# v1microcontroller.net
KiCad netlist of a schematic drawn in EAGLE
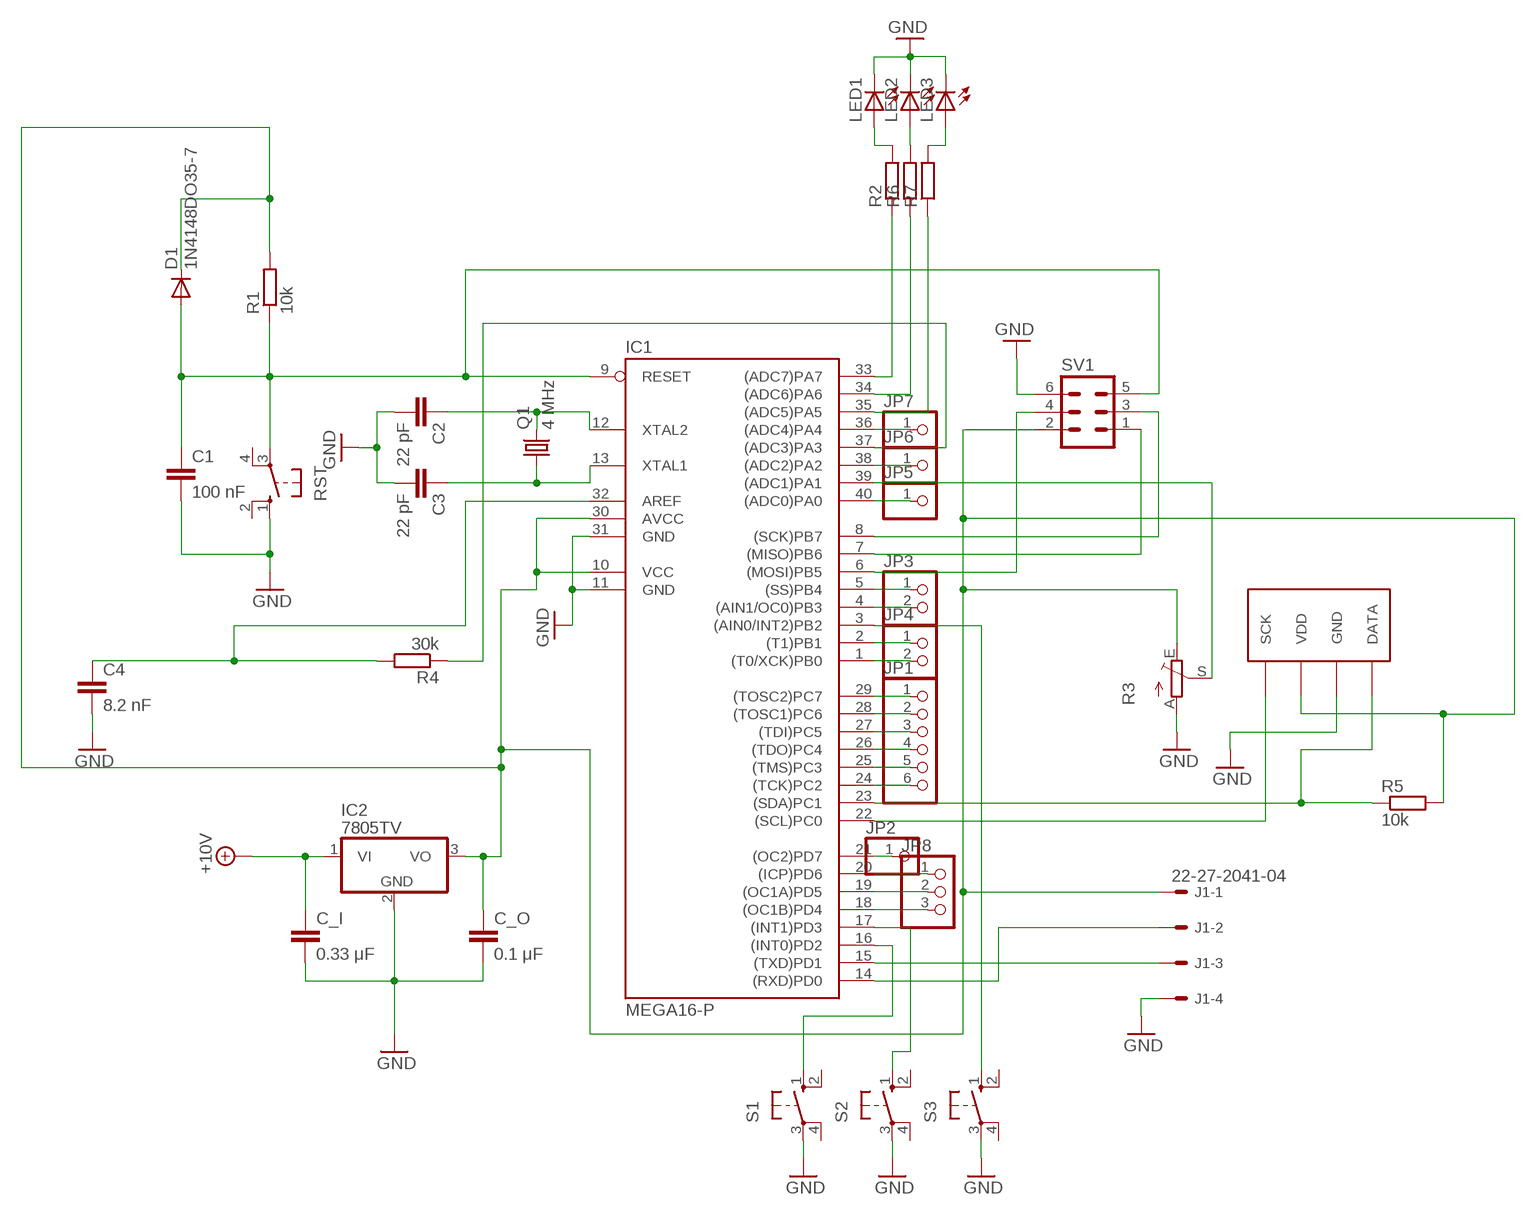
[diagram p0: schematic, sheet 1]

(export (version "E")
  (design (tool "Eeschema 10.0.6"))
  (components
    (comp (ref "C1")
      (value "100 nF")
      (footprint "eagle-import:C2.5-3")
      (libsource (lib "eagle-import") (part "C2,5-3"))
    )
    (comp (ref "C2")
      (value "22 pF")
      (footprint "eagle-import:C2.5-3")
      (libsource (lib "eagle-import") (part "C2,5-3"))
    )
    (comp (ref "C3")
      (value "22 pF")
      (footprint "eagle-import:C2.5-3")
      (libsource (lib "eagle-import") (part "C2,5-3"))
    )
    (comp (ref "C4")
      (value "8.2 nF")
      (footprint "eagle-import:C2.5-3")
      (libsource (lib "eagle-import") (part "C2,5-3"))
    )
    (comp (ref "C_I")
      (value "0.33 μF")
      (footprint "eagle-import:C2.5-3")
      (libsource (lib "eagle-import") (part "C2,5-3"))
    )
    (comp (ref "C_O")
      (value "0.1 μF")
      (footprint "eagle-import:C2.5-3")
      (libsource (lib "eagle-import") (part "C2,5-3"))
    )
    (comp (ref "D1")
      (value "1N4148DO35-7")
      (footprint "eagle-import:DO35-7")
      (libsource (lib "eagle-import") (part "1N4148DO35-7"))
    )
    (comp (ref "IC1")
      (value "MEGA16-P")
      (footprint "eagle-import:DIL40")
      (fields (field (name "MPN") "ATMEGA16-16PU"))
      (libsource (lib "eagle-import") (part "MEGA16-P"))
    )
    (comp (ref "IC2")
      (value "7805TV")
      (footprint "eagle-import:TO220V")
      (fields (field (name "SPICEPREFIX") "J"))
      (libsource (lib "eagle-import") (part "78TV05"))
    )
    (comp (ref "J1")
      (value "22-27-2041-04")
      (footprint "eagle-import:6410-04")
      (fields (field (name "MF") "MOLEX"))
      (libsource (lib "eagle-import") (part "22-?-0427-2041"))
    )
    (comp (ref "JP1")
      (value "PINHD-1X6")
      (footprint "eagle-import:1X06")
      (libsource (lib "eagle-import") (part "PINHD-1X6"))
    )
    (comp (ref "JP2")
      (value "PINHD-1X1")
      (footprint "eagle-import:1X01")
      (libsource (lib "eagle-import") (part "PINHD-1X1"))
    )
    (comp (ref "JP3")
      (value "PINHD-1X2")
      (footprint "eagle-import:1X02")
      (libsource (lib "eagle-import") (part "PINHD-1X2"))
    )
    (comp (ref "JP4")
      (value "PINHD-1X2")
      (footprint "eagle-import:1X02")
      (libsource (lib "eagle-import") (part "PINHD-1X2"))
    )
    (comp (ref "JP5")
      (value "PINHD-1X1")
      (footprint "eagle-import:1X01")
      (libsource (lib "eagle-import") (part "PINHD-1X1"))
    )
    (comp (ref "JP6")
      (value "PINHD-1X1")
      (footprint "eagle-import:1X01")
      (libsource (lib "eagle-import") (part "PINHD-1X1"))
    )
    (comp (ref "JP7")
      (value "PINHD-1X1")
      (footprint "eagle-import:1X01")
      (libsource (lib "eagle-import") (part "PINHD-1X1"))
    )
    (comp (ref "JP8")
      (value "PINHD-1X3")
      (footprint "eagle-import:1X03")
      (libsource (lib "eagle-import") (part "PINHD-1X3"))
    )
    (comp (ref "LED1")
      (value "LED5MM")
      (footprint "eagle-import:LED5MM")
      (libsource (lib "eagle-import") (part "LED5MM"))
    )
    (comp (ref "LED2")
      (value "LED5MM")
      (footprint "eagle-import:LED5MM")
      (libsource (lib "eagle-import") (part "LED5MM"))
    )
    (comp (ref "LED3")
      (value "LED5MM")
      (footprint "eagle-import:LED5MM")
      (libsource (lib "eagle-import") (part "LED5MM"))
    )
    (comp (ref "Q1")
      (value "4 MHz")
      (footprint "eagle-import:HC49U-V")
      (libsource (lib "eagle-import") (part "CRYSTALHC49U-V"))
    )
    (comp (ref "R1")
      (value "10k")
      (footprint "eagle-import:0204_5")
      (libsource (lib "eagle-import") (part "R-EU_0204/5"))
    )
    (comp (ref "R2")
      (value "R-EU_0204/5")
      (footprint "eagle-import:0204_5")
      (libsource (lib "eagle-import") (part "R-EU_0204/5"))
    )
    (comp (ref "R3")
      (value "TRIM_EU-CT6")
      (footprint "eagle-import:CT6")
      (libsource (lib "eagle-import") (part "TRIM_EU-CT6"))
    )
    (comp (ref "R4")
      (value "30k")
      (footprint "eagle-import:0204_5")
      (libsource (lib "eagle-import") (part "R-EU_0204/5"))
    )
    (comp (ref "R5")
      (value "10k")
      (footprint "eagle-import:0204_5")
      (libsource (lib "eagle-import") (part "R-EU_0204/5"))
    )
    (comp (ref "R6")
      (value "R-EU_0204/5")
      (footprint "eagle-import:0204_5")
      (libsource (lib "eagle-import") (part "R-EU_0204/5"))
    )
    (comp (ref "R7")
      (value "R-EU_0204/5")
      (footprint "eagle-import:0204_5")
      (libsource (lib "eagle-import") (part "R-EU_0204/5"))
    )
    (comp (ref "RST")
      (value "10-XX")
      (footprint "eagle-import:B3F-10XX")
      (fields (field (name "MPN") "B3F-1000"))
      (libsource (lib "eagle-import") (part "10-XX"))
    )
    (comp (ref "S1")
      (value "10-XX")
      (footprint "eagle-import:B3F-10XX")
      (fields (field (name "MPN") "B3F-1000"))
      (libsource (lib "eagle-import") (part "10-XX"))
    )
    (comp (ref "S2")
      (value "10-XX")
      (footprint "eagle-import:B3F-10XX")
      (fields (field (name "MPN") "B3F-1000"))
      (libsource (lib "eagle-import") (part "10-XX"))
    )
    (comp (ref "S3")
      (value "10-XX")
      (footprint "eagle-import:B3F-10XX")
      (fields (field (name "MPN") "B3F-1000"))
      (libsource (lib "eagle-import") (part "10-XX"))
    )
    (comp (ref "SV1")
      (value "ML6")
      (footprint "eagle-import:ML6")
      (libsource (lib "eagle-import") (part "ML6"))
    )
    (comp (ref "U$1")
      (value "SHT71")
      (footprint "eagle-import:SHT7X")
      (libsource (lib "eagle-import") (part "SHT71"))
    )
  )
  (nets
    (net (code "1") (name "+10V") (class "Default")
      (node (ref "C_I") (pin "1") (pinfunction "1_1") (pintype "passive"))
      (node (ref "IC2") (pin "1") (pinfunction "VI_1") (pintype "input"))
    )
    (net (code "2") (name "GND") (class "Default")
      (node (ref "C1") (pin "2") (pinfunction "2_2") (pintype "passive"))
      (node (ref "C2") (pin "2") (pinfunction "2_2") (pintype "passive"))
      (node (ref "C3") (pin "2") (pinfunction "2_2") (pintype "passive"))
      (node (ref "C4") (pin "2") (pinfunction "2_2") (pintype "passive"))
      (node (ref "C_I") (pin "2") (pinfunction "2_2") (pintype "passive"))
      (node (ref "C_O") (pin "2") (pinfunction "2_2") (pintype "passive"))
      (node (ref "IC1") (pin "11") (pinfunction "GND_11") (pintype "power_in"))
      (node (ref "IC1") (pin "31") (pinfunction "GND_31") (pintype "power_in"))
      (node (ref "IC2") (pin "2") (pinfunction "GND_2") (pintype "passive"))
      (node (ref "J1") (pin "4") (pinfunction "S_4") (pintype "passive"))
      (node (ref "LED1") (pin "K") (pinfunction "C_K") (pintype "passive"))
      (node (ref "LED2") (pin "K") (pinfunction "C_K") (pintype "passive"))
      (node (ref "LED3") (pin "K") (pinfunction "C_K") (pintype "passive"))
      (node (ref "R3") (pin "A") (pinfunction "A_A") (pintype "passive"))
      (node (ref "RST") (pin "1") (pinfunction "S_1") (pintype "passive"))
      (node (ref "S1") (pin "3") (pinfunction "P_3") (pintype "passive"))
      (node (ref "S2") (pin "3") (pinfunction "P_3") (pintype "passive"))
      (node (ref "S3") (pin "3") (pinfunction "P_3") (pintype "passive"))
      (node (ref "SV1") (pin "6") (pinfunction "6_6") (pintype "passive"))
      (node (ref "U$1") (pin "3") (pinfunction "GND_3") (pintype "power_in"))
    )
    (net (code "3") (name "Net-(IC1-(ADC0)PA0)") (class "Default")
      (node (ref "IC1") (pin "40") (pinfunction "(ADC0)PA0_40") (pintype "bidirectional"))
      (node (ref "JP5") (pin "1") (pinfunction "1_1") (pintype "passive"))
    )
    (net (code "4") (name "Net-(IC1-(ADC1)PA1)") (class "Default")
      (node (ref "IC1") (pin "39") (pinfunction "(ADC1)PA1_39") (pintype "bidirectional"))
      (node (ref "R3") (pin "S") (pinfunction "S_S") (pintype "passive"))
    )
    (net (code "5") (name "Net-(IC1-(ADC2)PA2)") (class "Default")
      (node (ref "IC1") (pin "38") (pinfunction "(ADC2)PA2_38") (pintype "bidirectional"))
      (node (ref "JP6") (pin "1") (pinfunction "1_1") (pintype "passive"))
    )
    (net (code "6") (name "Net-(IC1-(ADC3)PA3)") (class "Default")
      (node (ref "IC1") (pin "37") (pinfunction "(ADC3)PA3_37") (pintype "bidirectional"))
      (node (ref "R4") (pin "1") (pinfunction "1_1") (pintype "passive"))
    )
    (net (code "7") (name "Net-(IC1-(ADC4)PA4)") (class "Default")
      (node (ref "IC1") (pin "36") (pinfunction "(ADC4)PA4_36") (pintype "bidirectional"))
      (node (ref "JP7") (pin "1") (pinfunction "1_1") (pintype "passive"))
    )
    (net (code "8") (name "Net-(IC1-(ADC5)PA5)") (class "Default")
      (node (ref "IC1") (pin "35") (pinfunction "(ADC5)PA5_35") (pintype "bidirectional"))
      (node (ref "R7") (pin "1") (pinfunction "1_1") (pintype "passive"))
    )
    (net (code "9") (name "Net-(IC1-(ADC6)PA6)") (class "Default")
      (node (ref "IC1") (pin "34") (pinfunction "(ADC6)PA6_34") (pintype "bidirectional"))
      (node (ref "R6") (pin "1") (pinfunction "1_1") (pintype "passive"))
    )
    (net (code "10") (name "Net-(IC1-(ADC7)PA7)") (class "Default")
      (node (ref "IC1") (pin "33") (pinfunction "(ADC7)PA7_33") (pintype "bidirectional"))
      (node (ref "R2") (pin "1") (pinfunction "1_1") (pintype "passive"))
    )
    (net (code "11") (name "Net-(IC1-(AIN0{slash}INT2)PB2)") (class "Default")
      (node (ref "IC1") (pin "3") (pinfunction "(AIN0/INT2)PB2_3") (pintype "bidirectional"))
      (node (ref "S3") (pin "1") (pinfunction "S_1") (pintype "passive"))
    )
    (net (code "12") (name "Net-(IC1-(AIN1{slash}OC0)PB3)") (class "Default")
      (node (ref "IC1") (pin "4") (pinfunction "(AIN1/OC0)PB3_4") (pintype "bidirectional"))
      (node (ref "JP3") (pin "2") (pinfunction "2_2") (pintype "passive"))
    )
    (net (code "13") (name "Net-(IC1-(ICP)PD6)") (class "Default")
      (node (ref "IC1") (pin "20") (pinfunction "(ICP)PD6_20") (pintype "bidirectional"))
      (node (ref "JP8") (pin "1") (pinfunction "1_1") (pintype "passive"))
    )
    (net (code "14") (name "Net-(IC1-(INT0)PD2)") (class "Default")
      (node (ref "IC1") (pin "16") (pinfunction "(INT0)PD2_16") (pintype "bidirectional"))
      (node (ref "S1") (pin "1") (pinfunction "S_1") (pintype "passive"))
    )
    (net (code "15") (name "Net-(IC1-(INT1)PD3)") (class "Default")
      (node (ref "IC1") (pin "17") (pinfunction "(INT1)PD3_17") (pintype "bidirectional"))
      (node (ref "S2") (pin "1") (pinfunction "S_1") (pintype "passive"))
    )
    (net (code "16") (name "Net-(IC1-(MISO)PB6)") (class "Default")
      (node (ref "IC1") (pin "7") (pinfunction "(MISO)PB6_7") (pintype "bidirectional"))
      (node (ref "SV1") (pin "1") (pinfunction "1_1") (pintype "passive"))
    )
    (net (code "17") (name "Net-(IC1-(MOSI)PB5)") (class "Default")
      (node (ref "IC1") (pin "6") (pinfunction "(MOSI)PB5_6") (pintype "bidirectional"))
      (node (ref "SV1") (pin "4") (pinfunction "4_4") (pintype "passive"))
    )
    (net (code "18") (name "Net-(IC1-(OC1A)PD5)") (class "Default")
      (node (ref "IC1") (pin "19") (pinfunction "(OC1A)PD5_19") (pintype "bidirectional"))
      (node (ref "JP8") (pin "2") (pinfunction "2_2") (pintype "passive"))
    )
    (net (code "19") (name "Net-(IC1-(OC1B)PD4)") (class "Default")
      (node (ref "IC1") (pin "18") (pinfunction "(OC1B)PD4_18") (pintype "bidirectional"))
      (node (ref "JP8") (pin "3") (pinfunction "3_3") (pintype "passive"))
    )
    (net (code "20") (name "Net-(IC1-(OC2)PD7)") (class "Default")
      (node (ref "IC1") (pin "21") (pinfunction "(OC2)PD7_21") (pintype "bidirectional"))
      (node (ref "JP2") (pin "1") (pinfunction "1_1") (pintype "passive"))
    )
    (net (code "21") (name "Net-(IC1-(RXD)PD0)") (class "Default")
      (node (ref "IC1") (pin "14") (pinfunction "(RXD)PD0_14") (pintype "bidirectional"))
      (node (ref "J1") (pin "2") (pinfunction "S_2") (pintype "passive"))
    )
    (net (code "22") (name "Net-(IC1-(SCK)PB7)") (class "Default")
      (node (ref "IC1") (pin "8") (pinfunction "(SCK)PB7_8") (pintype "bidirectional"))
      (node (ref "SV1") (pin "3") (pinfunction "3_3") (pintype "passive"))
    )
    (net (code "23") (name "Net-(IC1-(SCL)PC0)") (class "Default")
      (node (ref "IC1") (pin "22") (pinfunction "(SCL)PC0_22") (pintype "bidirectional"))
      (node (ref "U$1") (pin "1") (pinfunction "SCK_1") (pintype "input"))
    )
    (net (code "24") (name "Net-(IC1-(SDA)PC1)") (class "Default")
      (node (ref "IC1") (pin "23") (pinfunction "(SDA)PC1_23") (pintype "bidirectional"))
      (node (ref "R5") (pin "1") (pinfunction "1_1") (pintype "passive"))
      (node (ref "U$1") (pin "4") (pinfunction "DATA_4") (pintype "bidirectional"))
    )
    (net (code "25") (name "Net-(IC1-(SS)PB4)") (class "Default")
      (node (ref "IC1") (pin "5") (pinfunction "(SS)PB4_5") (pintype "bidirectional"))
      (node (ref "JP3") (pin "1") (pinfunction "1_1") (pintype "passive"))
    )
    (net (code "26") (name "Net-(IC1-(T0{slash}XCK)PB0)") (class "Default")
      (node (ref "IC1") (pin "1") (pinfunction "(T0/XCK)PB0_1") (pintype "bidirectional"))
      (node (ref "JP4") (pin "2") (pinfunction "2_2") (pintype "passive"))
    )
    (net (code "27") (name "Net-(IC1-(T1)PB1)") (class "Default")
      (node (ref "IC1") (pin "2") (pinfunction "(T1)PB1_2") (pintype "bidirectional"))
      (node (ref "JP4") (pin "1") (pinfunction "1_1") (pintype "passive"))
    )
    (net (code "28") (name "Net-(IC1-(TCK)PC2)") (class "Default")
      (node (ref "IC1") (pin "24") (pinfunction "(TCK)PC2_24") (pintype "bidirectional"))
      (node (ref "JP1") (pin "6") (pinfunction "6_6") (pintype "passive"))
    )
    (net (code "29") (name "Net-(IC1-(TDI)PC5)") (class "Default")
      (node (ref "IC1") (pin "27") (pinfunction "(TDI)PC5_27") (pintype "bidirectional"))
      (node (ref "JP1") (pin "3") (pinfunction "3_3") (pintype "passive"))
    )
    (net (code "30") (name "Net-(IC1-(TDO)PC4)") (class "Default")
      (node (ref "IC1") (pin "26") (pinfunction "(TDO)PC4_26") (pintype "bidirectional"))
      (node (ref "JP1") (pin "4") (pinfunction "4_4") (pintype "passive"))
    )
    (net (code "31") (name "Net-(IC1-(TMS)PC3)") (class "Default")
      (node (ref "IC1") (pin "25") (pinfunction "(TMS)PC3_25") (pintype "bidirectional"))
      (node (ref "JP1") (pin "5") (pinfunction "5_5") (pintype "passive"))
    )
    (net (code "32") (name "Net-(IC1-(TOSC1)PC6)") (class "Default")
      (node (ref "IC1") (pin "28") (pinfunction "(TOSC1)PC6_28") (pintype "bidirectional"))
      (node (ref "JP1") (pin "2") (pinfunction "2_2") (pintype "passive"))
    )
    (net (code "33") (name "Net-(IC1-(TOSC2)PC7)") (class "Default")
      (node (ref "IC1") (pin "29") (pinfunction "(TOSC2)PC7_29") (pintype "bidirectional"))
      (node (ref "JP1") (pin "1") (pinfunction "1_1") (pintype "passive"))
    )
    (net (code "34") (name "Net-(IC1-(TXD)PD1)") (class "Default")
      (node (ref "IC1") (pin "15") (pinfunction "(TXD)PD1_15") (pintype "bidirectional"))
      (node (ref "J1") (pin "3") (pinfunction "S_3") (pintype "passive"))
    )
    (net (code "35") (name "Net-(IC1-AREF)") (class "Default")
      (node (ref "C4") (pin "1") (pinfunction "1_1") (pintype "passive"))
      (node (ref "IC1") (pin "32") (pinfunction "AREF_32") (pintype "passive"))
      (node (ref "R4") (pin "2") (pinfunction "2_2") (pintype "passive"))
    )
    (net (code "36") (name "Net-(IC1-AVCC)") (class "Default")
      (node (ref "C_O") (pin "1") (pinfunction "1_1") (pintype "passive"))
      (node (ref "D1") (pin "C") (pinfunction "C_C") (pintype "passive"))
      (node (ref "IC1") (pin "10") (pinfunction "VCC_10") (pintype "power_in"))
      (node (ref "IC1") (pin "30") (pinfunction "AVCC_30") (pintype "power_in"))
      (node (ref "IC2") (pin "3") (pinfunction "VO_3") (pintype "passive"))
      (node (ref "J1") (pin "1") (pinfunction "S_1") (pintype "passive"))
      (node (ref "R1") (pin "2") (pinfunction "2_2") (pintype "passive"))
      (node (ref "R3") (pin "E") (pinfunction "E_E") (pintype "passive"))
      (node (ref "R5") (pin "2") (pinfunction "2_2") (pintype "passive"))
      (node (ref "SV1") (pin "2") (pinfunction "2_2") (pintype "passive"))
      (node (ref "U$1") (pin "2") (pinfunction "VDD_2") (pintype "power_in"))
    )
    (net (code "37") (name "Net-(IC1-RESET)") (class "Default")
      (node (ref "C1") (pin "1") (pinfunction "1_1") (pintype "passive"))
      (node (ref "D1") (pin "A") (pinfunction "A_A") (pintype "passive"))
      (node (ref "IC1") (pin "9") (pinfunction "RESET_9") (pintype "input"))
      (node (ref "R1") (pin "1") (pinfunction "1_1") (pintype "passive"))
      (node (ref "RST") (pin "3") (pinfunction "P_3") (pintype "passive"))
      (node (ref "SV1") (pin "5") (pinfunction "5_5") (pintype "passive"))
    )
    (net (code "38") (name "Net-(IC1-XTAL1)") (class "Default")
      (node (ref "C3") (pin "1") (pinfunction "1_1") (pintype "passive"))
      (node (ref "IC1") (pin "13") (pinfunction "XTAL1_13") (pintype "bidirectional"))
      (node (ref "Q1") (pin "1") (pinfunction "1_1") (pintype "passive"))
    )
    (net (code "39") (name "Net-(IC1-XTAL2)") (class "Default")
      (node (ref "C2") (pin "1") (pinfunction "1_1") (pintype "passive"))
      (node (ref "IC1") (pin "12") (pinfunction "XTAL2_12") (pintype "bidirectional"))
      (node (ref "Q1") (pin "2") (pinfunction "2_2") (pintype "passive"))
    )
    (net (code "40") (name "Net-(LED1-PadA)") (class "Default")
      (node (ref "LED1") (pin "A") (pinfunction "A_A") (pintype "passive"))
      (node (ref "R2") (pin "2") (pinfunction "2_2") (pintype "passive"))
    )
    (net (code "41") (name "Net-(LED2-PadA)") (class "Default")
      (node (ref "LED2") (pin "A") (pinfunction "A_A") (pintype "passive"))
      (node (ref "R6") (pin "2") (pinfunction "2_2") (pintype "passive"))
    )
    (net (code "42") (name "Net-(LED3-PadA)") (class "Default")
      (node (ref "LED3") (pin "A") (pinfunction "A_A") (pintype "passive"))
      (node (ref "R7") (pin "2") (pinfunction "2_2") (pintype "passive"))
    )
    (net (code "43") (name "unconnected-(RST-P1-Pad4)") (class "Default")
      (node (ref "RST") (pin "4") (pinfunction "P1_4") (pintype "passive"))
    )
    (net (code "44") (name "unconnected-(RST-S1-Pad2)") (class "Default")
      (node (ref "RST") (pin "2") (pinfunction "S1_2") (pintype "passive"))
    )
    (net (code "45") (name "unconnected-(S1-P1-Pad4)") (class "Default")
      (node (ref "S1") (pin "4") (pinfunction "P1_4") (pintype "passive"))
    )
    (net (code "46") (name "unconnected-(S1-S1-Pad2)") (class "Default")
      (node (ref "S1") (pin "2") (pinfunction "S1_2") (pintype "passive"))
    )
    (net (code "47") (name "unconnected-(S2-P1-Pad4)") (class "Default")
      (node (ref "S2") (pin "4") (pinfunction "P1_4") (pintype "passive"))
    )
    (net (code "48") (name "unconnected-(S2-S1-Pad2)") (class "Default")
      (node (ref "S2") (pin "2") (pinfunction "S1_2") (pintype "passive"))
    )
    (net (code "49") (name "unconnected-(S3-P1-Pad4)") (class "Default")
      (node (ref "S3") (pin "4") (pinfunction "P1_4") (pintype "passive"))
    )
    (net (code "50") (name "unconnected-(S3-S1-Pad2)") (class "Default")
      (node (ref "S3") (pin "2") (pinfunction "S1_2") (pintype "passive"))
    )
  )
)
